# entireboard_v2_4layer.net
KiCad netlist of a schematic drawn in EAGLE
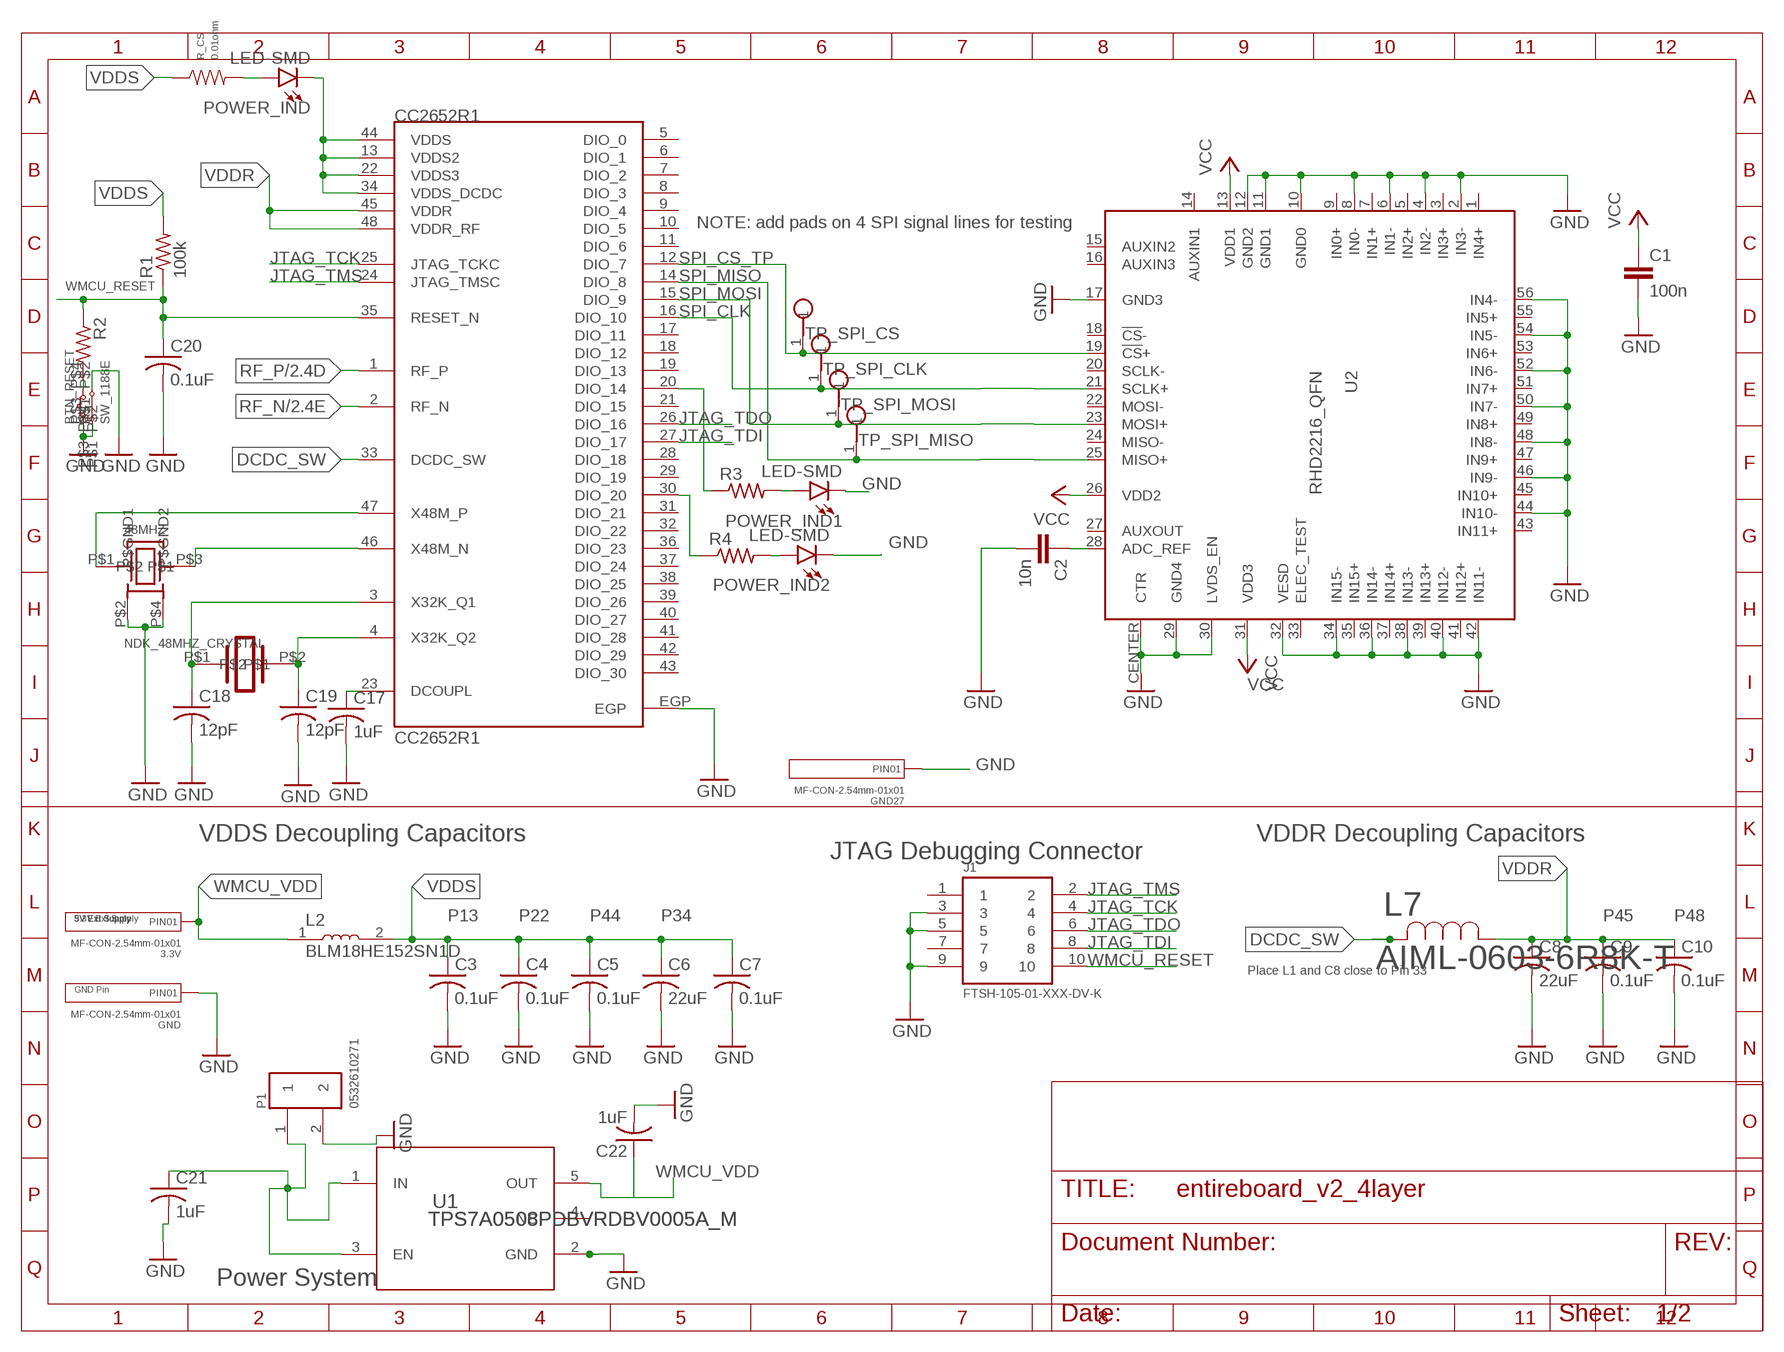
[diagram p0: schematic, sheet 1]
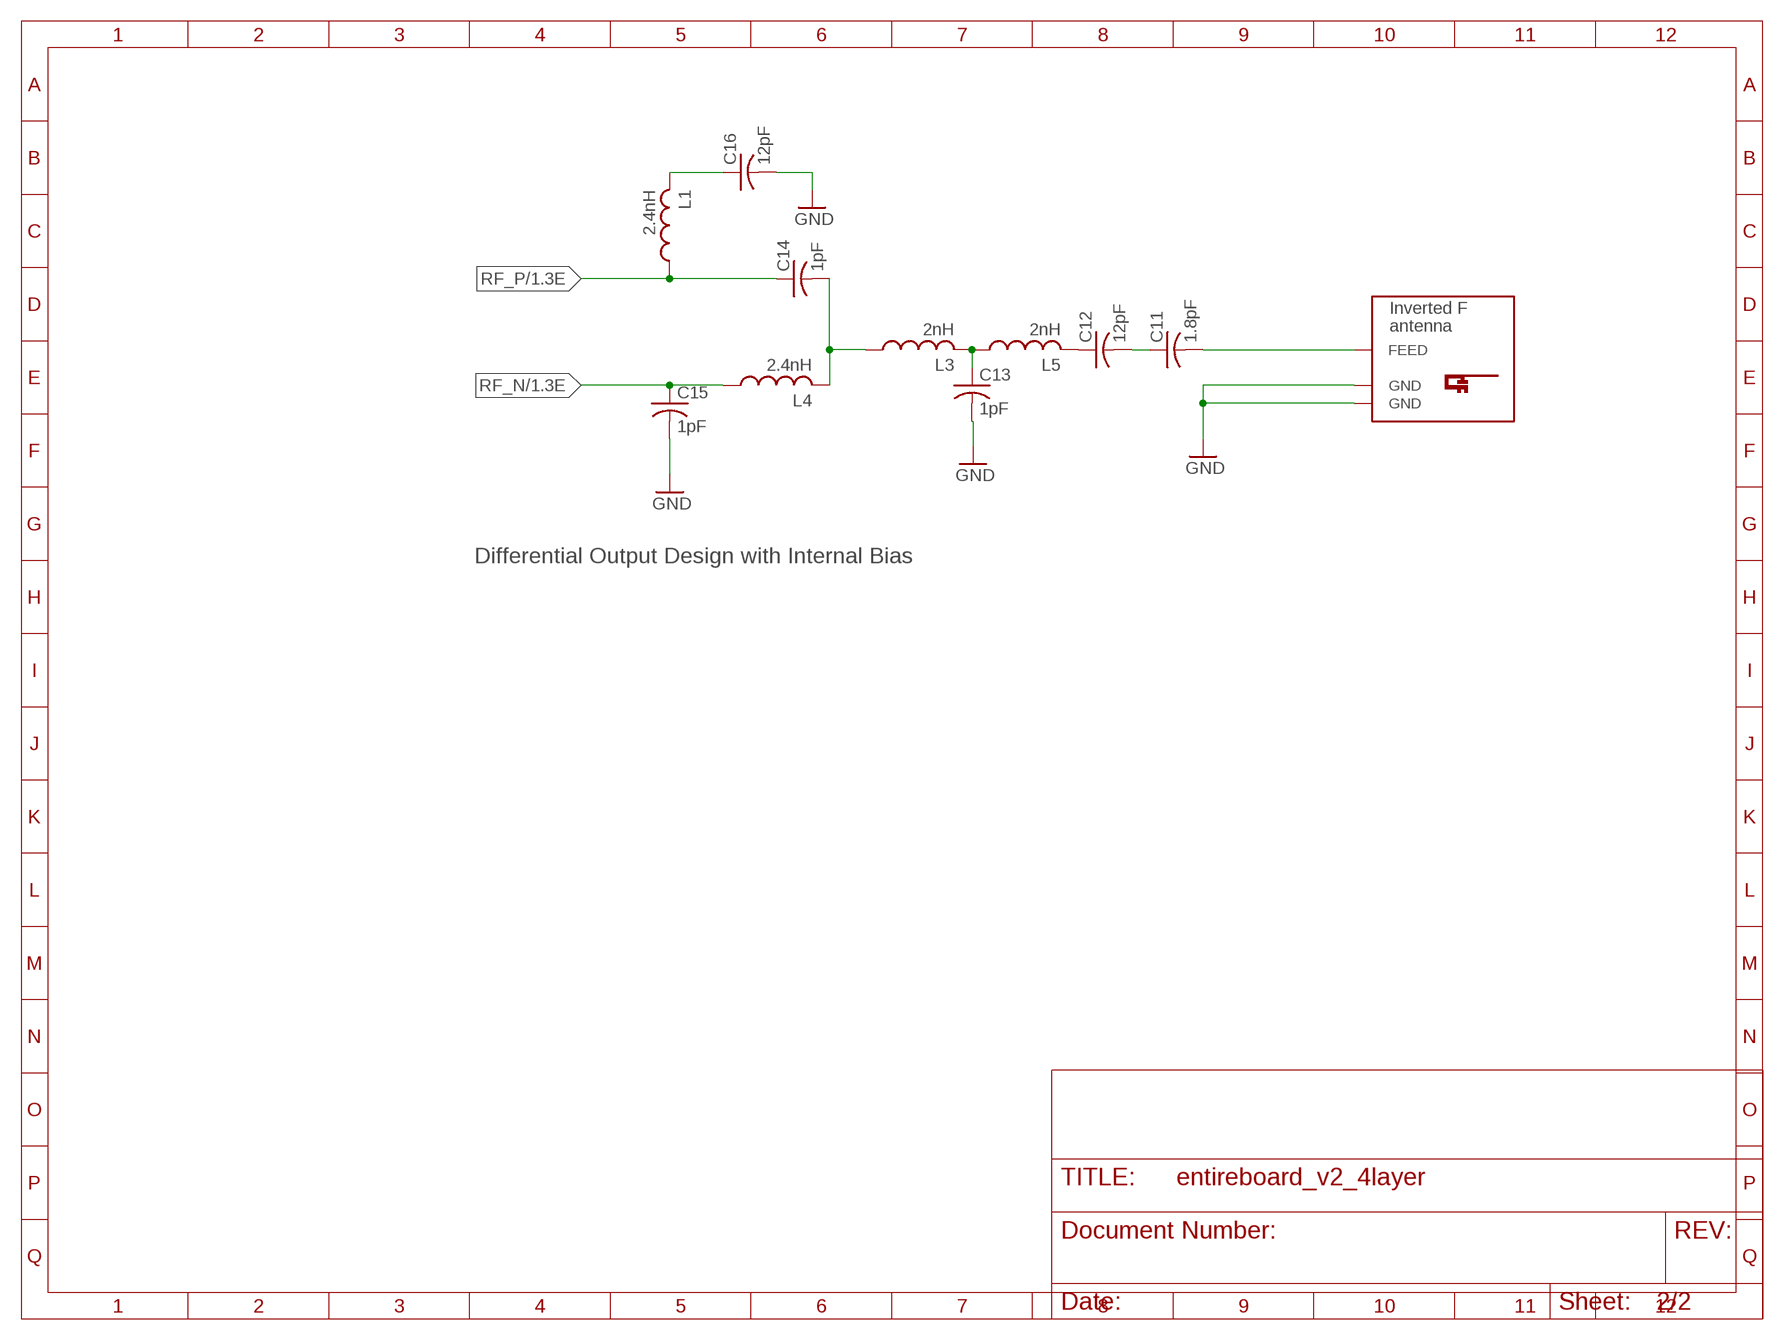
[diagram p1: schematic, sheet 2]

(export (version "E")
  (design (tool "Eeschema 10.0.6"))
  (components
    (comp (ref "3.3V")
      (value "MF-CON-2.54mm-01x01")
      (footprint "eagle-import:PTH_2.54MM_01X01")
      (fields (field (name "HOUSEPART") "YES"))
      (libsource (lib "eagle-import") (part "CON_01X01_PTH_2.54MM"))
    )
    (comp (ref "38.768KHZ")
      (value "EPSON_32.768KHZ_CRYSTAL")
      (footprint "eagle-import:2-SMD")
      (libsource (lib "eagle-import") (part "EPSON_32.768KHZ_CRYSTAL"))
    )
    (comp (ref "48MHZ")
      (value "NDK_48MHZ_CRYSTAL")
      (footprint "eagle-import:4-SMD")
      (libsource (lib "eagle-import") (part "NDK_48MHZ_CRYSTAL"))
    )
    (comp (ref "BTN_RESET")
      (value "SW_1188E")
      (footprint "eagle-import:SW_1188E")
      (libsource (lib "eagle-import") (part "SW_1188E"))
    )
    (comp (ref "C1")
      (value "100n")
      (footprint "eagle-import:0402")
      (libsource (lib "eagle-import") (part "C_0402"))
    )
    (comp (ref "C2")
      (value "10n")
      (footprint "eagle-import:0402")
      (libsource (lib "eagle-import") (part "C_0402"))
    )
    (comp (ref "C3")
      (value "0.1uF")
      (footprint "eagle-import:C0402")
      (libsource (lib "eagle-import") (part "C-USC0402"))
    )
    (comp (ref "C4")
      (value "0.1uF")
      (footprint "eagle-import:C0402")
      (libsource (lib "eagle-import") (part "C-USC0402"))
    )
    (comp (ref "C5")
      (value "0.1uF")
      (footprint "eagle-import:C0402")
      (libsource (lib "eagle-import") (part "C-USC0402"))
    )
    (comp (ref "C6")
      (value "22uF")
      (footprint "eagle-import:C0402")
      (libsource (lib "eagle-import") (part "C-USC0402"))
    )
    (comp (ref "C7")
      (value "0.1uF")
      (footprint "eagle-import:C0402")
      (libsource (lib "eagle-import") (part "C-USC0402"))
    )
    (comp (ref "C8")
      (value "22uF")
      (footprint "eagle-import:C0402")
      (libsource (lib "eagle-import") (part "C-USC0402"))
    )
    (comp (ref "C9")
      (value "0.1uF")
      (footprint "eagle-import:C0402")
      (libsource (lib "eagle-import") (part "C-USC0402"))
    )
    (comp (ref "C10")
      (value "0.1uF")
      (footprint "eagle-import:C0402")
      (libsource (lib "eagle-import") (part "C-USC0402"))
    )
    (comp (ref "C17")
      (value "1uF")
      (footprint "eagle-import:C0402")
      (libsource (lib "eagle-import") (part "C-USC0402"))
    )
    (comp (ref "C18")
      (value "12pF")
      (footprint "eagle-import:C0402")
      (libsource (lib "eagle-import") (part "C-USC0402"))
    )
    (comp (ref "C19")
      (value "12pF")
      (footprint "eagle-import:C0402")
      (libsource (lib "eagle-import") (part "C-USC0402"))
    )
    (comp (ref "C20")
      (value "0.1uF")
      (footprint "eagle-import:C0402")
      (libsource (lib "eagle-import") (part "C-USC0402"))
    )
    (comp (ref "C21")
      (value "1uF")
      (footprint "eagle-import:C0402")
      (libsource (lib "eagle-import") (part "C-USC0402"))
    )
    (comp (ref "C22")
      (value "1uF")
      (footprint "eagle-import:C0402")
      (libsource (lib "eagle-import") (part "C-USC0402"))
    )
    (comp (ref "CC2652R1")
      (value "CC2652R1")
      (footprint "eagle-import:CC2652R1_QFN-48")
      (libsource (lib "eagle-import") (part "CC2652R1"))
    )
    (comp (ref "GND")
      (value "MF-CON-2.54mm-01x01")
      (footprint "eagle-import:PTH_2.54MM_01X01")
      (fields (field (name "HOUSEPART") "YES"))
      (libsource (lib "eagle-import") (part "CON_01X01_PTH_2.54MM"))
    )
    (comp (ref "GND27")
      (value "MF-CON-2.54mm-01x01")
      (footprint "eagle-import:PTH_2.54MM_01X01")
      (fields (field (name "HOUSEPART") "YES"))
      (libsource (lib "eagle-import") (part "CON_01X01_PTH_2.54MM"))
    )
    (comp (ref "J1")
      (value "FTSH-105-01-XXX-DV-K")
      (footprint "eagle-import:FTSH-105-01-XXX-DV-K")
      (libsource (lib "eagle-import") (part "FTSH-105-01-XXX-DV-K"))
    )
    (comp (ref "L2")
      (value "BLM18HE152SN1D")
      (footprint "eagle-import:INDC1608X95")
      (fields (field (name "DIGI-KEY_PART_NUMBER") "490-5216-1-ND") (field (name "MF") "Murata Electronics"))
      (libsource (lib "eagle-import") (part "BLM18HE152SN1D"))
    )
    (comp (ref "L7")
      (value "AIML-0603-6R8K-T")
      (footprint "eagle-import:AIML-0603")
      (fields (field (name "MANUFACTURER_PART_NUMBER") "AIML06036R8KT"))
      (libsource (lib "eagle-import") (part "AIML-0603-6R8K-T"))
    )
    (comp (ref "P1")
      (value "0532610271")
      (footprint "eagle-import:MOLEX_0532610271")
      (fields (field (name "DIGI-KEY_PART_NUMBER") "WM7620CT-ND") (field (name "MF") "Molex, LLC"))
      (libsource (lib "eagle-import") (part "0532610271"))
    )
    (comp (ref "POWER_IND")
      (value "LED-SMD")
      (footprint "eagle-import:RHD2000_EVAL_BOARD_0402")
      (libsource (lib "eagle-import") (part "LED-SMD"))
    )
    (comp (ref "POWER_IND1")
      (value "LED-SMD")
      (footprint "eagle-import:RHD2000_EVAL_BOARD_0402")
      (libsource (lib "eagle-import") (part "LED-SMD"))
    )
    (comp (ref "POWER_IND2")
      (value "LED-SMD")
      (footprint "eagle-import:RHD2000_EVAL_BOARD_0402")
      (libsource (lib "eagle-import") (part "LED-SMD"))
    )
    (comp (ref "R1")
      (value "100k")
      (footprint "eagle-import:R0402")
      (libsource (lib "eagle-import") (part "R-US_R0402"))
    )
    (comp (ref "R2")
      (value "R-US_R0402")
      (footprint "eagle-import:R0402")
      (libsource (lib "eagle-import") (part "R-US_R0402"))
    )
    (comp (ref "R3")
      (value "R-US_R0402")
      (footprint "eagle-import:R0402")
      (libsource (lib "eagle-import") (part "R-US_R0402"))
    )
    (comp (ref "R4")
      (value "R-US_R0402")
      (footprint "eagle-import:R0402")
      (libsource (lib "eagle-import") (part "R-US_R0402"))
    )
    (comp (ref "R_CS")
      (value "0.01ohm")
      (footprint "eagle-import:R0402")
      (libsource (lib "eagle-import") (part "RESISTOR_0402"))
    )
    (comp (ref "TP_SPI_CLK")
      (value "RHD2000_EVAL_BOARD_TESTPOINT_SMALL")
      (footprint "eagle-import:RHD2000_EVAL_BOARD_TESTPOINT_SMALL")
      (libsource (lib "eagle-import") (part "RHD2000_EVAL_BOARD_TESTPOINT_SMALL"))
    )
    (comp (ref "TP_SPI_CS")
      (value "RHD2000_EVAL_BOARD_TESTPOINT_SMALL")
      (footprint "eagle-import:RHD2000_EVAL_BOARD_TESTPOINT_SMALL")
      (libsource (lib "eagle-import") (part "RHD2000_EVAL_BOARD_TESTPOINT_SMALL"))
    )
    (comp (ref "TP_SPI_MISO")
      (value "RHD2000_EVAL_BOARD_TESTPOINT_SMALL")
      (footprint "eagle-import:RHD2000_EVAL_BOARD_TESTPOINT_SMALL")
      (libsource (lib "eagle-import") (part "RHD2000_EVAL_BOARD_TESTPOINT_SMALL"))
    )
    (comp (ref "TP_SPI_MOSI")
      (value "RHD2000_EVAL_BOARD_TESTPOINT_SMALL")
      (footprint "eagle-import:RHD2000_EVAL_BOARD_TESTPOINT_SMALL")
      (libsource (lib "eagle-import") (part "RHD2000_EVAL_BOARD_TESTPOINT_SMALL"))
    )
    (comp (ref "U1")
      (value "TPS7A0508PDBVRDBV0005A_M")
      (footprint "eagle-import:DBV0005A_M")
      (libsource (lib "eagle-import") (part "TPS7A0508PDBVRDBV0005A_M"))
    )
    (comp (ref "U2")
      (value "RHD2216_QFN")
      (footprint "eagle-import:QFN56_8_X_8_LARGE")
      (libsource (lib "eagle-import") (part "RHD2216_QFN"))
    )
    (comp (ref "C11")
      (value "1.8pF")
      (footprint "eagle-import:C0402")
      (libsource (lib "eagle-import") (part "C-USC0402"))
    )
    (comp (ref "C12")
      (value "12pF")
      (footprint "eagle-import:C0402")
      (libsource (lib "eagle-import") (part "C-USC0402"))
    )
    (comp (ref "C13")
      (value "1pF")
      (footprint "eagle-import:C0402")
      (libsource (lib "eagle-import") (part "C-USC0402"))
    )
    (comp (ref "C14")
      (value "1pF")
      (footprint "eagle-import:C0402")
      (libsource (lib "eagle-import") (part "C-USC0402"))
    )
    (comp (ref "C15")
      (value "1pF")
      (footprint "eagle-import:C0402")
      (libsource (lib "eagle-import") (part "C-USC0402"))
    )
    (comp (ref "C16")
      (value "12pF")
      (footprint "eagle-import:C0402")
      (libsource (lib "eagle-import") (part "C-USC0402"))
    )
    (comp (ref "L1")
      (value "2.4nH")
      (footprint "eagle-import:L0201")
      (libsource (lib "eagle-import") (part "L-USL0201"))
    )
    (comp (ref "L3")
      (value "2nH")
      (footprint "eagle-import:L0201")
      (libsource (lib "eagle-import") (part "L-USL0201"))
    )
    (comp (ref "L4")
      (value "2.4nH")
      (footprint "eagle-import:L0201")
      (libsource (lib "eagle-import") (part "L-USL0201"))
    )
    (comp (ref "L5")
      (value "2nH")
      (footprint "eagle-import:L0201")
      (libsource (lib "eagle-import") (part "L-USL0201"))
    )
    (comp (ref "U$2")
      (value "INVERTED_F_ANTENNA+0")
      (footprint "eagle-import:DN007+0")
      (libsource (lib "eagle-import") (part "INVERTED_F_ANTENNA+0"))
    )
  )
  (nets
    (net (code "1") (name "DCDC_SW") (class "Default")
      (node (ref "CC2652R1") (pin "33") (pinfunction "DCDC_SW_33") (pintype "bidirectional"))
      (node (ref "L7") (pin "2") (pinfunction "2_2") (pintype "passive"))
    )
    (net (code "2") (name "GND") (class "Default")
      (node (ref "48MHZ") (pin "P$2") (pinfunction "P$GND1_P$2") (pintype "bidirectional"))
      (node (ref "48MHZ") (pin "P$4") (pinfunction "P$GND2_P$4") (pintype "bidirectional"))
      (node (ref "BTN_RESET") (pin "P$1") (pinfunction "P$1_P$1") (pintype "bidirectional"))
      (node (ref "BTN_RESET") (pin "P$2") (pinfunction "P$2_P$2") (pintype "bidirectional"))
      (node (ref "BTN_RESET") (pin "P$3") (pinfunction "P$3_P$3") (pintype "bidirectional"))
      (node (ref "C1") (pin "2") (pinfunction "2_2") (pintype "passive"))
      (node (ref "C10") (pin "2") (pinfunction "2_2") (pintype "passive"))
      (node (ref "C13") (pin "2") (pinfunction "2_2") (pintype "passive"))
      (node (ref "C15") (pin "2") (pinfunction "2_2") (pintype "passive"))
      (node (ref "C16") (pin "2") (pinfunction "2_2") (pintype "passive"))
      (node (ref "C17") (pin "2") (pinfunction "2_2") (pintype "passive"))
      (node (ref "C18") (pin "2") (pinfunction "2_2") (pintype "passive"))
      (node (ref "C19") (pin "2") (pinfunction "2_2") (pintype "passive"))
      (node (ref "C2") (pin "2") (pinfunction "2_2") (pintype "passive"))
      (node (ref "C20") (pin "2") (pinfunction "2_2") (pintype "passive"))
      (node (ref "C21") (pin "2") (pinfunction "2_2") (pintype "passive"))
      (node (ref "C22") (pin "2") (pinfunction "2_2") (pintype "passive"))
      (node (ref "C3") (pin "2") (pinfunction "2_2") (pintype "passive"))
      (node (ref "C4") (pin "2") (pinfunction "2_2") (pintype "passive"))
      (node (ref "C5") (pin "2") (pinfunction "2_2") (pintype "passive"))
      (node (ref "C6") (pin "2") (pinfunction "2_2") (pintype "passive"))
      (node (ref "C7") (pin "2") (pinfunction "2_2") (pintype "passive"))
      (node (ref "C8") (pin "2") (pinfunction "2_2") (pintype "passive"))
      (node (ref "C9") (pin "2") (pinfunction "2_2") (pintype "passive"))
      (node (ref "CC2652R1") (pin "EGP") (pinfunction "EGP_EGP") (pintype "bidirectional"))
      (node (ref "GND") (pin "P$1") (pinfunction "PIN1_P$1") (pintype "bidirectional"))
      (node (ref "GND27") (pin "P$1") (pinfunction "PIN1_P$1") (pintype "bidirectional"))
      (node (ref "J1") (pin "3") (pinfunction "3_3") (pintype "bidirectional"))
      (node (ref "J1") (pin "5") (pinfunction "5_5") (pintype "bidirectional"))
      (node (ref "J1") (pin "9") (pinfunction "9_9") (pintype "bidirectional"))
      (node (ref "P1") (pin "2") (pinfunction "2_2") (pintype "passive"))
      (node (ref "POWER_IND1") (pin "2") (pinfunction "C_2") (pintype "passive"))
      (node (ref "POWER_IND2") (pin "2") (pinfunction "C_2") (pintype "passive"))
      (node (ref "U$2") (pin "GND") (pinfunction "GND_GND") (pintype "bidirectional"))
      (node (ref "U$2") (pin "GND@1") (pinfunction "GND_GND@1") (pintype "bidirectional"))
      (node (ref "U1") (pin "2") (pinfunction "GND_2") (pintype "power_in"))
      (node (ref "U2") (pin "10") (pinfunction "GND0_10") (pintype "input"))
      (node (ref "U2") (pin "11") (pinfunction "GND1_11") (pintype "power_in"))
      (node (ref "U2") (pin "12") (pinfunction "GND2_12") (pintype "power_in"))
      (node (ref "U2") (pin "17") (pinfunction "GND3_17") (pintype "power_in"))
      (node (ref "U2") (pin "2") (pinfunction "IN3-_2") (pintype "input"))
      (node (ref "U2") (pin "29") (pinfunction "GND4_29") (pintype "power_in"))
      (node (ref "U2") (pin "30") (pinfunction "LVDS_EN_30") (pintype "input"))
      (node (ref "U2") (pin "32") (pinfunction "VESD_32") (pintype "power_in"))
      (node (ref "U2") (pin "34") (pinfunction "IN15-_34") (pintype "input"))
      (node (ref "U2") (pin "36") (pinfunction "IN14-_36") (pintype "input"))
      (node (ref "U2") (pin "38") (pinfunction "IN13-_38") (pintype "input"))
      (node (ref "U2") (pin "4") (pinfunction "IN2-_4") (pintype "input"))
      (node (ref "U2") (pin "40") (pinfunction "IN12-_40") (pintype "input"))
      (node (ref "U2") (pin "42") (pinfunction "IN11-_42") (pintype "input"))
      (node (ref "U2") (pin "44") (pinfunction "IN10-_44") (pintype "input"))
      (node (ref "U2") (pin "46") (pinfunction "IN9-_46") (pintype "input"))
      (node (ref "U2") (pin "48") (pinfunction "IN8-_48") (pintype "input"))
      (node (ref "U2") (pin "50") (pinfunction "IN7-_50") (pintype "input"))
      (node (ref "U2") (pin "52") (pinfunction "IN6-_52") (pintype "input"))
      (node (ref "U2") (pin "54") (pinfunction "IN5-_54") (pintype "input"))
      (node (ref "U2") (pin "56") (pinfunction "IN4-_56") (pintype "input"))
      (node (ref "U2") (pin "6") (pinfunction "IN1-_6") (pintype "input"))
      (node (ref "U2") (pin "8") (pinfunction "IN0-_8") (pintype "input"))
      (node (ref "U2") (pin "CENTER") (pinfunction "CTR_CENTER") (pintype "power_in"))
    )
    (net (code "3") (name "JTAG_TCK") (class "Default")
      (node (ref "CC2652R1") (pin "25") (pinfunction "JTAG_TCKC_25") (pintype "bidirectional"))
      (node (ref "J1") (pin "4") (pinfunction "4_4") (pintype "bidirectional"))
    )
    (net (code "4") (name "JTAG_TDI") (class "Default")
      (node (ref "CC2652R1") (pin "27") (pinfunction "DIO_17_27") (pintype "bidirectional"))
      (node (ref "J1") (pin "8") (pinfunction "8_8") (pintype "bidirectional"))
    )
    (net (code "5") (name "JTAG_TDO") (class "Default")
      (node (ref "CC2652R1") (pin "26") (pinfunction "DIO_16_26") (pintype "bidirectional"))
      (node (ref "J1") (pin "6") (pinfunction "6_6") (pintype "bidirectional"))
    )
    (net (code "6") (name "JTAG_TMS") (class "Default")
      (node (ref "CC2652R1") (pin "24") (pinfunction "JTAG_TMSC_24") (pintype "bidirectional"))
      (node (ref "J1") (pin "2") (pinfunction "2_2") (pintype "bidirectional"))
    )
    (net (code "7") (name "NC") (class "Default")
      (node (ref "U1") (pin "4") (pinfunction "NC_4") (pintype "power_in"))
    )
    (net (code "8") (name "Net-(48MHZ-P$2)") (class "Default")
      (node (ref "48MHZ") (pin "P$3") (pinfunction "P$2_P$3") (pintype "bidirectional"))
      (node (ref "CC2652R1") (pin "46") (pinfunction "X48M_N_46") (pintype "bidirectional"))
    )
    (net (code "9") (name "Net-(BTN_RESET-PadP$4)") (class "Default")
      (node (ref "BTN_RESET") (pin "P$4") (pinfunction "P$4_P$4") (pintype "bidirectional"))
      (node (ref "R2") (pin "2") (pinfunction "2_2") (pintype "passive"))
    )
    (net (code "10") (name "Net-(C11-Pad1)") (class "Default")
      (node (ref "C11") (pin "1") (pinfunction "1_1") (pintype "passive"))
      (node (ref "C12") (pin "2") (pinfunction "2_2") (pintype "passive"))
    )
    (net (code "11") (name "Net-(C11-Pad2)") (class "Default")
      (node (ref "C11") (pin "2") (pinfunction "2_2") (pintype "passive"))
      (node (ref "U$2") (pin "FEED") (pinfunction "FEED_FEED") (pintype "bidirectional"))
    )
    (net (code "12") (name "Net-(C12-Pad1)") (class "Default")
      (node (ref "C12") (pin "1") (pinfunction "1_1") (pintype "passive"))
      (node (ref "L5") (pin "2") (pinfunction "2_2") (pintype "passive"))
    )
    (net (code "13") (name "Net-(C13-Pad1)") (class "Default")
      (node (ref "C13") (pin "1") (pinfunction "1_1") (pintype "passive"))
      (node (ref "L3") (pin "2") (pinfunction "2_2") (pintype "passive"))
      (node (ref "L5") (pin "1") (pinfunction "1_1") (pintype "passive"))
    )
    (net (code "14") (name "Net-(C14-Pad2)") (class "Default")
      (node (ref "C14") (pin "2") (pinfunction "2_2") (pintype "passive"))
      (node (ref "L3") (pin "1") (pinfunction "1_1") (pintype "passive"))
      (node (ref "L4") (pin "2") (pinfunction "2_2") (pintype "passive"))
    )
    (net (code "15") (name "Net-(C16-Pad1)") (class "Default")
      (node (ref "C16") (pin "1") (pinfunction "1_1") (pintype "passive"))
      (node (ref "L1") (pin "2") (pinfunction "2_2") (pintype "passive"))
    )
    (net (code "16") (name "Net-(CC2652R1-DCOUPL)") (class "Default")
      (node (ref "C17") (pin "1") (pinfunction "1_1") (pintype "passive"))
      (node (ref "CC2652R1") (pin "23") (pinfunction "DCOUPL_23") (pintype "bidirectional"))
    )
    (net (code "17") (name "Net-(CC2652R1-DIO_14)") (class "Default")
      (node (ref "CC2652R1") (pin "20") (pinfunction "DIO_14_20") (pintype "bidirectional"))
      (node (ref "R3") (pin "1") (pinfunction "1_1") (pintype "passive"))
    )
    (net (code "18") (name "Net-(CC2652R1-DIO_20)") (class "Default")
      (node (ref "CC2652R1") (pin "30") (pinfunction "DIO_20_30") (pintype "bidirectional"))
      (node (ref "R4") (pin "1") (pinfunction "1_1") (pintype "passive"))
    )
    (net (code "19") (name "Net-(CC2652R1-X32K_Q1)") (class "Default")
      (node (ref "38.768KHZ") (pin "P$1") (pinfunction "P$1_P$1") (pintype "bidirectional"))
      (node (ref "C18") (pin "1") (pinfunction "1_1") (pintype "passive"))
      (node (ref "CC2652R1") (pin "3") (pinfunction "X32K_Q1_3") (pintype "bidirectional"))
    )
    (net (code "20") (name "Net-(CC2652R1-X32K_Q2)") (class "Default")
      (node (ref "38.768KHZ") (pin "P$2") (pinfunction "P$2_P$2") (pintype "bidirectional"))
      (node (ref "C19") (pin "1") (pinfunction "1_1") (pintype "passive"))
      (node (ref "CC2652R1") (pin "4") (pinfunction "X32K_Q2_4") (pintype "bidirectional"))
    )
    (net (code "21") (name "Net-(CC2652R1-X48M_P)") (class "Default")
      (node (ref "48MHZ") (pin "P$1") (pinfunction "P$1_P$1") (pintype "bidirectional"))
      (node (ref "CC2652R1") (pin "47") (pinfunction "X48M_P_47") (pintype "bidirectional"))
    )
    (net (code "22") (name "Net-(POWER_IND-A)") (class "Default")
      (node (ref "POWER_IND") (pin "1") (pinfunction "A_1") (pintype "passive"))
      (node (ref "R_CS") (pin "P$2") (pinfunction "P$2_P$2") (pintype "passive"))
    )
    (net (code "23") (name "Net-(POWER_IND1-A)") (class "Default")
      (node (ref "POWER_IND1") (pin "1") (pinfunction "A_1") (pintype "passive"))
      (node (ref "R3") (pin "2") (pinfunction "2_2") (pintype "passive"))
    )
    (net (code "24") (name "Net-(POWER_IND2-A)") (class "Default")
      (node (ref "POWER_IND2") (pin "1") (pinfunction "A_1") (pintype "passive"))
      (node (ref "R4") (pin "2") (pinfunction "2_2") (pintype "passive"))
    )
    (net (code "25") (name "Net-(U1-EN)") (class "Default")
      (node (ref "C21") (pin "1") (pinfunction "1_1") (pintype "passive"))
      (node (ref "P1") (pin "1") (pinfunction "1_1") (pintype "passive"))
      (node (ref "U1") (pin "1") (pinfunction "IN_1") (pintype "power_in"))
      (node (ref "U1") (pin "3") (pinfunction "EN_3") (pintype "input"))
    )
    (net (code "26") (name "Net-(U2-ADC_REF)") (class "Default")
      (node (ref "C2") (pin "1") (pinfunction "1_1") (pintype "passive"))
      (node (ref "U2") (pin "28") (pinfunction "ADC_REF_28") (pintype "passive"))
    )
    (net (code "27") (name "RF_N") (class "Default")
      (node (ref "C15") (pin "1") (pinfunction "1_1") (pintype "passive"))
      (node (ref "CC2652R1") (pin "2") (pinfunction "RF_N_2") (pintype "bidirectional"))
      (node (ref "L4") (pin "1") (pinfunction "1_1") (pintype "passive"))
    )
    (net (code "28") (name "RF_P") (class "Default")
      (node (ref "C14") (pin "1") (pinfunction "1_1") (pintype "passive"))
      (node (ref "CC2652R1") (pin "1") (pinfunction "RF_P_1") (pintype "bidirectional"))
      (node (ref "L1") (pin "1") (pinfunction "1_1") (pintype "passive"))
    )
    (net (code "29") (name "SPI_CLK") (class "Default")
      (node (ref "CC2652R1") (pin "16") (pinfunction "DIO_10_16") (pintype "bidirectional"))
      (node (ref "TP_SPI_CLK") (pin "1") (pinfunction "1_1") (pintype "passive"))
      (node (ref "U2") (pin "21") (pinfunction "SCLK+_21") (pintype "input"))
    )
    (net (code "30") (name "SPI_CS_TP") (class "Default")
      (node (ref "CC2652R1") (pin "12") (pinfunction "DIO_7_12") (pintype "bidirectional"))
      (node (ref "TP_SPI_CS") (pin "1") (pinfunction "1_1") (pintype "passive"))
      (node (ref "U2") (pin "19") (pinfunction "~{CS}+_19") (pintype "input"))
    )
    (net (code "31") (name "SPI_MISO") (class "Default")
      (node (ref "CC2652R1") (pin "14") (pinfunction "DIO_8_14") (pintype "bidirectional"))
      (node (ref "TP_SPI_MISO") (pin "1") (pinfunction "1_1") (pintype "passive"))
      (node (ref "U2") (pin "25") (pinfunction "MISO+_25") (pintype "output"))
    )
    (net (code "32") (name "SPI_MOSI") (class "Default")
      (node (ref "CC2652R1") (pin "15") (pinfunction "DIO_9_15") (pintype "bidirectional"))
      (node (ref "TP_SPI_MOSI") (pin "1") (pinfunction "1_1") (pintype "passive"))
      (node (ref "U2") (pin "23") (pinfunction "MOSI+_23") (pintype "input"))
    )
    (net (code "33") (name "VCC") (class "Default")
      (node (ref "C1") (pin "1") (pinfunction "1_1") (pintype "passive"))
      (node (ref "U2") (pin "13") (pinfunction "VDD1_13") (pintype "power_in"))
      (node (ref "U2") (pin "26") (pinfunction "VDD2_26") (pintype "power_in"))
      (node (ref "U2") (pin "31") (pinfunction "VDD3_31") (pintype "power_in"))
    )
    (net (code "34") (name "VDDR") (class "Default")
      (node (ref "C10") (pin "1") (pinfunction "1_1") (pintype "passive"))
      (node (ref "C8") (pin "1") (pinfunction "1_1") (pintype "passive"))
      (node (ref "C9") (pin "1") (pinfunction "1_1") (pintype "passive"))
      (node (ref "CC2652R1") (pin "45") (pinfunction "VDDR_45") (pintype "bidirectional"))
      (node (ref "CC2652R1") (pin "48") (pinfunction "VDDR_RF_48") (pintype "bidirectional"))
      (node (ref "L7") (pin "1") (pinfunction "1_1") (pintype "passive"))
    )
    (net (code "35") (name "VDDS") (class "Default")
      (node (ref "C3") (pin "1") (pinfunction "1_1") (pintype "passive"))
      (node (ref "C4") (pin "1") (pinfunction "1_1") (pintype "passive"))
      (node (ref "C5") (pin "1") (pinfunction "1_1") (pintype "passive"))
      (node (ref "C6") (pin "1") (pinfunction "1_1") (pintype "passive"))
      (node (ref "C7") (pin "1") (pinfunction "1_1") (pintype "passive"))
      (node (ref "CC2652R1") (pin "13") (pinfunction "VDDS2_13") (pintype "bidirectional"))
      (node (ref "CC2652R1") (pin "22") (pinfunction "VDDS3_22") (pintype "bidirectional"))
      (node (ref "CC2652R1") (pin "34") (pinfunction "VDDS_DCDC_34") (pintype "bidirectional"))
      (node (ref "CC2652R1") (pin "44") (pinfunction "VDDS_44") (pintype "bidirectional"))
      (node (ref "L2") (pin "2") (pinfunction "2_2") (pintype "passive"))
      (node (ref "POWER_IND") (pin "2") (pinfunction "C_2") (pintype "passive"))
      (node (ref "R1") (pin "2") (pinfunction "2_2") (pintype "passive"))
      (node (ref "R_CS") (pin "P$1") (pinfunction "P$1_P$1") (pintype "passive"))
    )
    (net (code "36") (name "WMCU_RESET") (class "Default")
      (node (ref "C20") (pin "1") (pinfunction "1_1") (pintype "passive"))
      (node (ref "CC2652R1") (pin "35") (pinfunction "RESET_N_35") (pintype "bidirectional"))
      (node (ref "J1") (pin "10") (pinfunction "10_10") (pintype "bidirectional"))
      (node (ref "R1") (pin "1") (pinfunction "1_1") (pintype "passive"))
      (node (ref "R2") (pin "1") (pinfunction "1_1") (pintype "passive"))
    )
    (net (code "37") (name "WMCU_VDD") (class "Default")
      (node (ref "3.3V") (pin "P$1") (pinfunction "PIN1_P$1") (pintype "bidirectional"))
      (node (ref "C22") (pin "1") (pinfunction "1_1") (pintype "passive"))
      (node (ref "L2") (pin "1") (pinfunction "1_1") (pintype "passive"))
      (node (ref "U1") (pin "5") (pinfunction "OUT_5") (pintype "power_in"))
    )
    (net (code "38") (name "unconnected-(CC2652R1-DIO_0-Pad5)") (class "Default")
      (node (ref "CC2652R1") (pin "5") (pinfunction "DIO_0_5") (pintype "bidirectional"))
    )
    (net (code "39") (name "unconnected-(CC2652R1-DIO_1-Pad6)") (class "Default")
      (node (ref "CC2652R1") (pin "6") (pinfunction "DIO_1_6") (pintype "bidirectional"))
    )
    (net (code "40") (name "unconnected-(CC2652R1-DIO_2-Pad7)") (class "Default")
      (node (ref "CC2652R1") (pin "7") (pinfunction "DIO_2_7") (pintype "bidirectional"))
    )
    (net (code "41") (name "unconnected-(CC2652R1-DIO_3-Pad8)") (class "Default")
      (node (ref "CC2652R1") (pin "8") (pinfunction "DIO_3_8") (pintype "bidirectional"))
    )
    (net (code "42") (name "unconnected-(CC2652R1-DIO_4-Pad9)") (class "Default")
      (node (ref "CC2652R1") (pin "9") (pinfunction "DIO_4_9") (pintype "bidirectional"))
    )
    (net (code "43") (name "unconnected-(CC2652R1-DIO_5-Pad10)") (class "Default")
      (node (ref "CC2652R1") (pin "10") (pinfunction "DIO_5_10") (pintype "bidirectional"))
    )
    (net (code "44") (name "unconnected-(CC2652R1-DIO_6-Pad11)") (class "Default")
      (node (ref "CC2652R1") (pin "11") (pinfunction "DIO_6_11") (pintype "bidirectional"))
    )
    (net (code "45") (name "unconnected-(CC2652R1-DIO_11-Pad17)") (class "Default")
      (node (ref "CC2652R1") (pin "17") (pinfunction "DIO_11_17") (pintype "bidirectional"))
    )
    (net (code "46") (name "unconnected-(CC2652R1-DIO_12-Pad18)") (class "Default")
      (node (ref "CC2652R1") (pin "18") (pinfunction "DIO_12_18") (pintype "bidirectional"))
    )
    (net (code "47") (name "unconnected-(CC2652R1-DIO_13-Pad19)") (class "Default")
      (node (ref "CC2652R1") (pin "19") (pinfunction "DIO_13_19") (pintype "bidirectional"))
    )
    (net (code "48") (name "unconnected-(CC2652R1-DIO_15-Pad21)") (class "Default")
      (node (ref "CC2652R1") (pin "21") (pinfunction "DIO_15_21") (pintype "bidirectional"))
    )
    (net (code "49") (name "unconnected-(CC2652R1-DIO_18-Pad28)") (class "Default")
      (node (ref "CC2652R1") (pin "28") (pinfunction "DIO_18_28") (pintype "bidirectional"))
    )
    (net (code "50") (name "unconnected-(CC2652R1-DIO_19-Pad29)") (class "Default")
      (node (ref "CC2652R1") (pin "29") (pinfunction "DIO_19_29") (pintype "bidirectional"))
    )
    (net (code "51") (name "unconnected-(CC2652R1-DIO_21-Pad31)") (class "Default")
      (node (ref "CC2652R1") (pin "31") (pinfunction "DIO_21_31") (pintype "bidirectional"))
    )
    (net (code "52") (name "unconnected-(CC2652R1-DIO_22-Pad32)") (class "Default")
      (node (ref "CC2652R1") (pin "32") (pinfunction "DIO_22_32") (pintype "bidirectional"))
    )
    (net (code "53") (name "unconnected-(CC2652R1-DIO_23-Pad36)") (class "Default")
      (node (ref "CC2652R1") (pin "36") (pinfunction "DIO_23_36") (pintype "bidirectional"))
    )
    (net (code "54") (name "unconnected-(CC2652R1-DIO_24-Pad37)") (class "Default")
      (node (ref "CC2652R1") (pin "37") (pinfunction "DIO_24_37") (pintype "bidirectional"))
    )
    (net (code "55") (name "unconnected-(CC2652R1-DIO_25-Pad38)") (class "Default")
      (node (ref "CC2652R1") (pin "38") (pinfunction "DIO_25_38") (pintype "bidirectional"))
    )
    (net (code "56") (name "unconnected-(CC2652R1-DIO_26-Pad39)") (class "Default")
      (node (ref "CC2652R1") (pin "39") (pinfunction "DIO_26_39") (pintype "bidirectional"))
    )
    (net (code "57") (name "unconnected-(CC2652R1-DIO_27-Pad40)") (class "Default")
      (node (ref "CC2652R1") (pin "40") (pinfunction "DIO_27_40") (pintype "bidirectional"))
    )
    (net (code "58") (name "unconnected-(CC2652R1-DIO_28-Pad41)") (class "Default")
      (node (ref "CC2652R1") (pin "41") (pinfunction "DIO_28_41") (pintype "bidirectional"))
    )
    (net (code "59") (name "unconnected-(CC2652R1-DIO_29-Pad42)") (class "Default")
      (node (ref "CC2652R1") (pin "42") (pinfunction "DIO_29_42") (pintype "bidirectional"))
    )
    (net (code "60") (name "unconnected-(CC2652R1-DIO_30-Pad43)") (class "Default")
      (node (ref "CC2652R1") (pin "43") (pinfunction "DIO_30_43") (pintype "bidirectional"))
    )
    (net (code "61") (name "unconnected-(J1-Pad1)") (class "Default")
      (node (ref "J1") (pin "1") (pinfunction "1_1") (pintype "bidirectional"))
    )
    (net (code "62") (name "unconnected-(J1-Pad7)") (class "Default")
      (node (ref "J1") (pin "7") (pinfunction "7_7") (pintype "bidirectional"))
    )
    (net (code "63") (name "unconnected-(U2-AUXIN1-Pad14)") (class "Default")
      (node (ref "U2") (pin "14") (pinfunction "AUXIN1_14") (pintype "input"))
    )
    (net (code "64") (name "unconnected-(U2-AUXIN2-Pad15)") (class "Default")
      (node (ref "U2") (pin "15") (pinfunction "AUXIN2_15") (pintype "input"))
    )
    (net (code "65") (name "unconnected-(U2-AUXIN3-Pad16)") (class "Default")
      (node (ref "U2") (pin "16") (pinfunction "AUXIN3_16") (pintype "input"))
    )
    (net (code "66") (name "unconnected-(U2-AUXOUT-Pad27)") (class "Default")
      (node (ref "U2") (pin "27") (pinfunction "AUXOUT_27") (pintype "tri_state"))
    )
    (net (code "67") (name "unconnected-(U2-ELEC_TEST-Pad33)") (class "Default")
      (node (ref "U2") (pin "33") (pinfunction "ELEC_TEST_33") (pintype "input"))
    )
    (net (code "68") (name "unconnected-(U2-IN0+-Pad9)") (class "Default")
      (node (ref "U2") (pin "9") (pinfunction "IN0+_9") (pintype "input"))
    )
    (net (code "69") (name "unconnected-(U2-IN1+-Pad7)") (class "Default")
      (node (ref "U2") (pin "7") (pinfunction "IN1+_7") (pintype "input"))
    )
    (net (code "70") (name "unconnected-(U2-IN2+-Pad5)") (class "Default")
      (node (ref "U2") (pin "5") (pinfunction "IN2+_5") (pintype "input"))
    )
    (net (code "71") (name "unconnected-(U2-IN3+-Pad3)") (class "Default")
      (node (ref "U2") (pin "3") (pinfunction "IN3+_3") (pintype "input"))
    )
    (net (code "72") (name "unconnected-(U2-IN4+-Pad1)") (class "Default")
      (node (ref "U2") (pin "1") (pinfunction "IN4+_1") (pintype "input"))
    )
    (net (code "73") (name "unconnected-(U2-IN5+-Pad55)") (class "Default")
      (node (ref "U2") (pin "55") (pinfunction "IN5+_55") (pintype "input"))
    )
    (net (code "74") (name "unconnected-(U2-IN6+-Pad53)") (class "Default")
      (node (ref "U2") (pin "53") (pinfunction "IN6+_53") (pintype "input"))
    )
    (net (code "75") (name "unconnected-(U2-IN7+-Pad51)") (class "Default")
      (node (ref "U2") (pin "51") (pinfunction "IN7+_51") (pintype "input"))
    )
    (net (code "76") (name "unconnected-(U2-IN8+-Pad49)") (class "Default")
      (node (ref "U2") (pin "49") (pinfunction "IN8+_49") (pintype "input"))
    )
    (net (code "77") (name "unconnected-(U2-IN9+-Pad47)") (class "Default")
      (node (ref "U2") (pin "47") (pinfunction "IN9+_47") (pintype "input"))
    )
    (net (code "78") (name "unconnected-(U2-IN10+-Pad45)") (class "Default")
      (node (ref "U2") (pin "45") (pinfunction "IN10+_45") (pintype "input"))
    )
    (net (code "79") (name "unconnected-(U2-IN11+-Pad43)") (class "Default")
      (node (ref "U2") (pin "43") (pinfunction "IN11+_43") (pintype "input"))
    )
    (net (code "80") (name "unconnected-(U2-IN12+-Pad41)") (class "Default")
      (node (ref "U2") (pin "41") (pinfunction "IN12+_41") (pintype "input"))
    )
    (net (code "81") (name "unconnected-(U2-IN13+-Pad39)") (class "Default")
      (node (ref "U2") (pin "39") (pinfunction "IN13+_39") (pintype "input"))
    )
    (net (code "82") (name "unconnected-(U2-IN14+-Pad37)") (class "Default")
      (node (ref "U2") (pin "37") (pinfunction "IN14+_37") (pintype "input"))
    )
    (net (code "83") (name "unconnected-(U2-IN15+-Pad35)") (class "Default")
      (node (ref "U2") (pin "35") (pinfunction "IN15+_35") (pintype "input"))
    )
    (net (code "84") (name "unconnected-(U2-MISO--Pad24)") (class "Default")
      (node (ref "U2") (pin "24") (pinfunction "MISO-_24") (pintype "output"))
    )
    (net (code "85") (name "unconnected-(U2-MOSI--Pad22)") (class "Default")
      (node (ref "U2") (pin "22") (pinfunction "MOSI-_22") (pintype "input"))
    )
    (net (code "86") (name "unconnected-(U2-SCLK--Pad20)") (class "Default")
      (node (ref "U2") (pin "20") (pinfunction "SCLK-_20") (pintype "input"))
    )
    (net (code "87") (name "unconnected-(U2-~{CS}--Pad18)") (class "Default")
      (node (ref "U2") (pin "18") (pinfunction "~{CS}-_18") (pintype "input"))
    )
  )
)
